# DriveInterface.net
KiCad netlist of a schematic drawn in Altium Designer
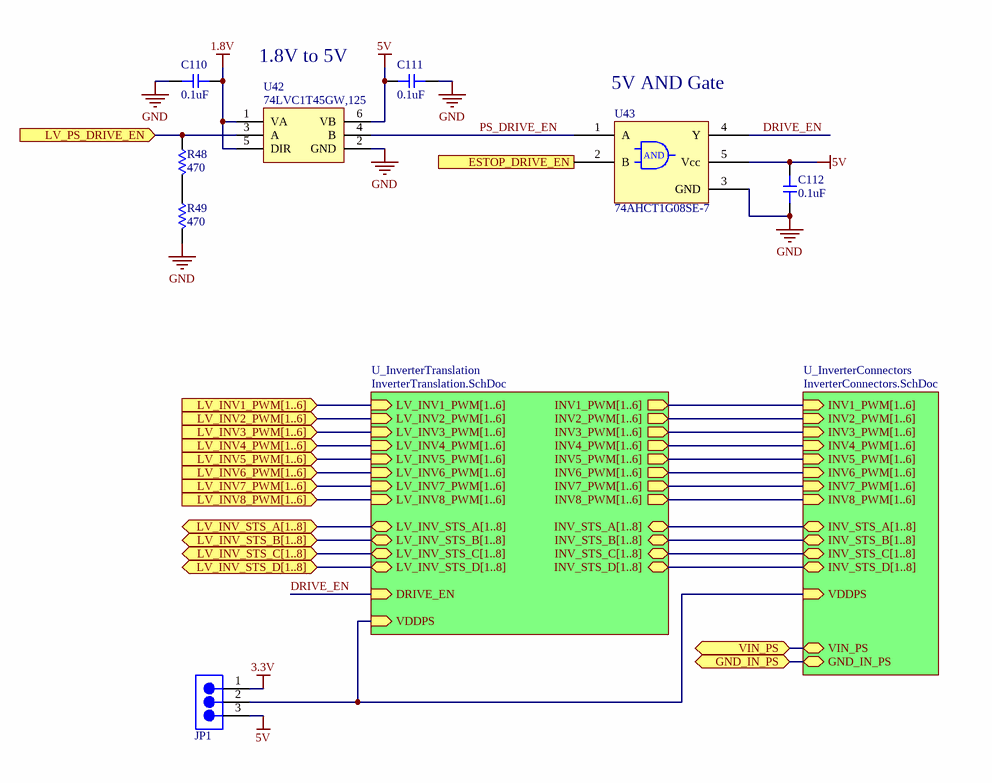
[diagram p0: DriveInterface.SchDoc]

(export (version "E")
  (design (tool "Eeschema 10.0.6"))
  (components
    (comp (ref "C110")
      (value "0.1uF")
      (footprint "0603-CAP")
      (description "Capacitor")
      (libsource (lib "AMDC") (part "Capacitor"))
    )
    (comp (ref "C111")
      (value "0.1uF")
      (footprint "0603-CAP")
      (description "Capacitor")
      (libsource (lib "AMDC") (part "Capacitor"))
    )
    (comp (ref "C112")
      (value "0.1uF")
      (footprint "0603-CAP")
      (description "Capacitor")
      (libsource (lib "AMDC") (part "Capacitor"))
    )
    (comp (ref "JP1")
      (value "Jumper3")
      (footprint "PIN_HEADER_1X3")
      (libsource (lib "AMDC") (part "Jumper3"))
    )
    (comp (ref "R48")
      (value "470")
      (footprint "0603-RES")
      (description "Resistor")
      (libsource (lib "AMDC") (part "Resistor"))
    )
    (comp (ref "R49")
      (value "470")
      (footprint "0603-RES")
      (description "Resistor")
      (libsource (lib "AMDC") (part "Resistor"))
    )
    (comp (ref "U42")
      (value "74LVC1T45GW,125")
      (footprint "SOT65P210X110-6N")
      (description "TXRX XLATING DUAL 3ST 6TSSOP")
      (libsource (lib "AMDC") (part "74LVC1T45GW,125"))
    )
    (comp (ref "U43")
      (value "74AHCT1G08SE-7")
      (footprint "SOT65P210X110-5N")
      (description "IC GATE AND 1CH 2-INP SOT353")
      (libsource (lib "AMDC") (part "74AHCT1G08SE-7"))
    )
  )
  (nets
    (net (code "81") (name "/DRIVE_EN") (class "Default")
      (node (ref "U43") (pin "4") (pinfunction "Y_4") (pintype "passive"))
    )
    (net (code "82") (name "/ESTOP_DRIVE_EN") (class "Default")
      (node (ref "U43") (pin "2") (pinfunction "B_2") (pintype "passive"))
    )
    (net (code "108") (name "/LV_PS_DRIVE_EN") (class "Default")
      (node (ref "R48") (pin "1") (pinfunction "1_1") (pintype "passive"))
      (node (ref "U42") (pin "3") (pinfunction "A_3") (pintype "passive"))
    )
    (net (code "109") (name "/PS_DRIVE_EN") (class "Default")
      (node (ref "U42") (pin "4") (pinfunction "B_4") (pintype "passive"))
      (node (ref "U43") (pin "1") (pinfunction "A_1") (pintype "passive"))
    )
    (net (code "110") (name "/VDDPS") (class "Default")
      (node (ref "JP1") (pin "2") (pinfunction "75_2") (pintype "passive"))
    )
    (net (code "112") (name "1.8V") (class "Default")
      (node (ref "C110") (pin "2") (pinfunction "2_2") (pintype "passive"))
      (node (ref "U42") (pin "1") (pinfunction "VA_1") (pintype "passive"))
      (node (ref "U42") (pin "5") (pinfunction "DIR_5") (pintype "passive"))
    )
    (net (code "113") (name "3.3V") (class "Default")
      (node (ref "JP1") (pin "1") (pinfunction "76_1") (pintype "passive"))
    )
    (net (code "114") (name "5V") (class "Default")
      (node (ref "C111") (pin "1") (pinfunction "1_1") (pintype "passive"))
      (node (ref "C112") (pin "2") (pinfunction "2_2") (pintype "passive"))
      (node (ref "JP1") (pin "3") (pinfunction "75_3") (pintype "passive"))
      (node (ref "U42") (pin "6") (pinfunction "VB_6") (pintype "passive"))
      (node (ref "U43") (pin "5") (pinfunction "Vcc_5") (pintype "passive"))
    )
    (net (code "115") (name "GND") (class "Default")
      (node (ref "C110") (pin "1") (pinfunction "1_1") (pintype "passive"))
      (node (ref "C111") (pin "2") (pinfunction "2_2") (pintype "passive"))
      (node (ref "C112") (pin "1") (pinfunction "1_1") (pintype "passive"))
      (node (ref "R49") (pin "2") (pinfunction "2_2") (pintype "passive"))
      (node (ref "U42") (pin "2") (pinfunction "GND_2") (pintype "passive"))
      (node (ref "U43") (pin "3") (pinfunction "GND_3") (pintype "passive"))
    )
    (net (code "116") (name "Net-(R48-Pad2)") (class "Default")
      (node (ref "R48") (pin "2") (pinfunction "2_2") (pintype "passive"))
      (node (ref "R49") (pin "1") (pinfunction "1_1") (pintype "passive"))
    )
  )
)
